# Charging.net
KiCad netlist of a schematic drawn in Altium Designer
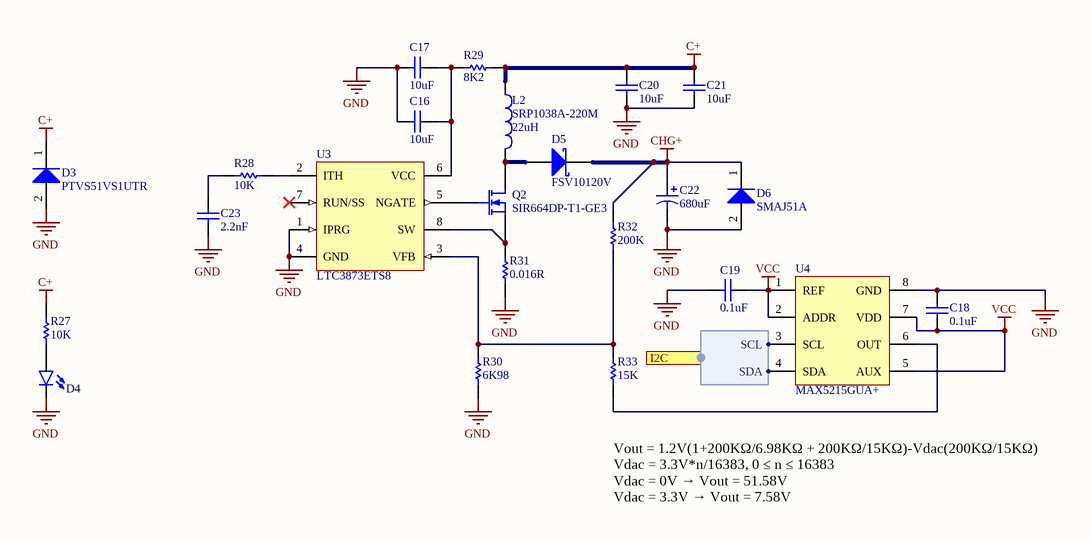
[diagram p0: Charging.SchDoc]

(export (version "E")
  (design (tool "Eeschema 10.0.6"))
  (components
    (comp (ref "C16")
      (value "10uF")
      (footprint "C0603[1608X92]")
      (description "10uF 16V 10% 0603 (1608 Metric)")
      (fields (field (name "PARTNUMBER") "GRM188R61C106KAALD") (field (name "MANUFACTURER") "Murata"))
      (libsource (lib "Capacitors") (part "CAP_10uF_16V_0603_10%"))
    )
    (comp (ref "C17")
      (value "10uF")
      (footprint "C0603[1608X92]")
      (description "10uF 16V 10% 0603 (1608 Metric)")
      (fields (field (name "PARTNUMBER") "GRM188R61C106KAALD") (field (name "MANUFACTURER") "Murata"))
      (libsource (lib "Capacitors") (part "CAP_10uF_16V_0603_10%"))
    )
    (comp (ref "C18")
      (value "0.1uF")
      (footprint "C0603[1608X92]")
      (description "0.1uF 6.3V 10% 0603 (1608 Metric)")
      (fields (field (name "PARTNUMBER") "GRM188R70J104KA01D") (field (name "MANUFACTURER") "Murata"))
      (libsource (lib "Capacitors") (part "CAP_0.1uF_6.3V_0603_10%"))
    )
    (comp (ref "C19")
      (value "0.1uF")
      (footprint "C0603[1608X92]")
      (description "0.1uF 6.3V 10% 0603 (1608 Metric)")
      (fields (field (name "PARTNUMBER") "GRM188R70J104KA01D") (field (name "MANUFACTURER") "Murata"))
      (libsource (lib "Capacitors") (part "CAP_0.1uF_6.3V_0603_10%"))
    )
    (comp (ref "C20")
      (value "10uF")
      (footprint "C1206[3216X160]")
      (description "10uF 50V 20% 1206 (3216 Metric)")
      (fields (field (name "TOLERANCE") "20%") (field (name "PARTNUMBER") "UMK316BBJ106ML-T"))
      (libsource (lib "Capacitors") (part "CAP_10uF_50V_1206_20%"))
    )
    (comp (ref "C21")
      (value "10uF")
      (footprint "C1206[3216X160]")
      (description "10uF 50V 20% 1206 (3216 Metric)")
      (fields (field (name "TOLERANCE") "20%") (field (name "PARTNUMBER") "UMK316BBJ106ML-T"))
      (libsource (lib "Capacitors") (part "CAP_10uF_50V_1206_20%"))
    )
    (comp (ref "C22")
      (value "680uF")
      (footprint "CAP-ELECTROLYTIC[10.0x12.6]")
      (description "180uF 50V 20%")
      (fields (field (name "PARTNUMBER") "PCR1H181MCL1GS") (field (name "MANUFACTURER") "Nichicon"))
      (libsource (lib "Capacitors") (part "CAP_180uF_50V_20%"))
    )
    (comp (ref "C23")
      (value "2.2nF")
      (footprint "C0603[1608X92]")
      (description "2.2nF 50V 5% 0603 (1608 Metric)")
      (fields (field (name "PARTNUMBER") "GRM1885C1H222JA01D") (field (name "MANUFACTURER") "Murata"))
      (libsource (lib "Capacitors") (part "CAP_2.2nF_50V_0603_5%"))
    )
    (comp (ref "D3")
      (value "PTVS51VS1UTR")
      (footprint "SOD-123W")
      (fields (field (name "PARTNUMBER") "PTVS51VS1UTR,115") (field (name "MANUFACTURER") "NXP"))
      (libsource (lib "Diodes") (part "PTVS51VS1UTR,115"))
    )
    (comp (ref "D4")
      (value "LED_0603_GREEN_5mA")
      (footprint "LED0603")
      (fields (field (name "PARTNUMBER") "LTST-C193TGKT-5A") (field (name "MANUFACTURER") "Lite-On Inc."))
      (libsource (lib "LEDs") (part "LED_0603_GREEN_5mA"))
    )
    (comp (ref "D5")
      (value "FSV10120V")
      (footprint "TO-277")
      (description "Schottky Diodes & Rectifiers 10 Amp 120V Schottky Rectifier")
      (fields (field (name "MANUFACTURER") "Fairchild Semiconductor"))
      (libsource (lib "Diodes") (part "FSV10120V"))
    )
    (comp (ref "D6")
      (value "SMAJ51A")
      (footprint "DO-214AC")
      (fields (field (name "PARTNUMBER") "SMAJ51A-E3/61") (field (name "MANUFACTURER") "Vishay"))
      (libsource (lib "Diodes") (part "SMAJ51A-E3/61"))
    )
    (comp (ref "L2")
      (value "SRP1038A-220M")
      (footprint "SRP1038A")
      (description "22uH 20% 7A 1038")
      (fields (field (name "ALTIUM_VALUE") "22uH") (field (name "MANUFACTURER") "Bourns"))
      (libsource (lib "Inductors") (part "SRP1038A-220M"))
    )
    (comp (ref "Q2")
      (value "SIR664DP-T1-GE3")
      (footprint "PowerPak-8")
      (description "N-Channel MOSFET")
      (fields (field (name "MANUFACTURER") "Vishay"))
      (libsource (lib "MOSFETs") (part "SIR664DP-T1-GE3"))
    )
    (comp (ref "R27")
      (value "10K")
      (footprint "R0603[1608]")
      (description "10K 0.25W 1% 0603 (1005 Metric)")
      (fields (field (name "POWER") "0.25W") (field (name "TOLERANCE") "1%"))
      (libsource (lib "Resistors") (part "RES_10K_0603_1%"))
    )
    (comp (ref "R28")
      (value "10K")
      (footprint "R0603[1608]")
      (description "10K 0.25W 1% 0603 (1005 Metric)")
      (fields (field (name "MANUFACTURER") "Vishay") (field (name "PARTNUMBER") "RCS060310K0FKEA"))
      (libsource (lib "Resistors") (part "RES_10K_0603_1%"))
    )
    (comp (ref "R29")
      (value "8K2")
      (footprint "R0603[1608]")
      (description "8K2 0.25W 1% 0603 (1005 Metric)")
      (fields (field (name "MANUFACTURER") "Vishay") (field (name "PARTNUMBER") "CRCW06038K20FKEAHP"))
      (libsource (lib "Resistors") (part "RES_8K2_0603_1%"))
    )
    (comp (ref "R30")
      (value "6K98")
      (footprint "R0603[1608]")
      (description "6K98 0.25W 1% 0603 (1005 Metric)")
      (fields (field (name "MANUFACTURER") "Vishay / Dale") (field (name "PARTNUMBER") "CRCW06036K98FKEAHP"))
      (libsource (lib "Resistors") (part "RES_6K98_0603_1%"))
    )
    (comp (ref "R31")
      (value "0.016R")
      (footprint "R1206[3216]")
      (description "0.016R 1W 1% 1206 (3216 Metric)")
      (fields (field (name "POWER") "1W") (field (name "TOLERANCE") "1%"))
      (libsource (lib "Resistors") (part "RES_0.016R_1206_1%"))
    )
    (comp (ref "R32")
      (value "200K")
      (footprint "R0603[1608]")
      (description "200K 0.25W 1% 0603 (1005 Metric)")
      (fields (field (name "MANUFACTURER") "Rohm Semiconductor") (field (name "PARTNUMBER") "ESR03EZPJ204"))
      (libsource (lib "Resistors") (part "RES_200K_0603_1%"))
    )
    (comp (ref "R33")
      (value "15K")
      (footprint "R0603[1608]")
      (description "15K 0.25W 1% 0603 (1005 Metric)")
      (fields (field (name "MANUFACTURER") "Vishay / Dale") (field (name "PARTNUMBER") "CRCW060315K0FKEAHP"))
      (libsource (lib "Resistors") (part "RES_15K_0603_1%"))
    )
    (comp (ref "U3")
      (value "LTC3873ETS8")
      (footprint "SOT-23-8")
      (fields (field (name "PARTNUMBER") "LTC3873ETS8#PBF") (field (name "MANUFACTURER") "Linear Technology"))
      (libsource (lib "ICs") (part "LTC3873ETS8"))
    )
    (comp (ref "U4")
      (value "MAX5215GUA+")
      (footprint "MSOP-8")
      (description "14 Bit Digital to Analog Converter")
      (fields (field (name "MANUFACTURER") "Maxim Integrated"))
      (libsource (lib "ICs") (part "MAX5215GUA+"))
    )
  )
  (nets
    (net (code "2") (name "/SCL") (class "Default")
      (node (ref "U4") (pin "3") (pinfunction "SCL_3") (pintype "passive"))
    )
    (net (code "3") (name "/SDA") (class "Default")
      (node (ref "U4") (pin "4") (pinfunction "SDA_4") (pintype "passive"))
    )
    (net (code "5") (name "C+") (class "Default")
      (node (ref "C20") (pin "2") (pinfunction "2_2") (pintype "passive"))
      (node (ref "C21") (pin "2") (pinfunction "2_2") (pintype "passive"))
      (node (ref "D3") (pin "1") (pinfunction "K_1") (pintype "passive"))
      (node (ref "L2") (pin "1") (pinfunction "1_1") (pintype "passive"))
      (node (ref "R27") (pin "2") (pinfunction "2_2") (pintype "passive"))
      (node (ref "R29") (pin "2") (pinfunction "2_2") (pintype "passive"))
    )
    (net (code "6") (name "CHG+") (class "Default")
      (node (ref "C22") (pin "1") (pinfunction "1_1") (pintype "passive"))
      (node (ref "D5") (pin "1") (pinfunction "K_1") (pintype "passive"))
      (node (ref "D6") (pin "1") (pinfunction "K_1") (pintype "passive"))
      (node (ref "R32") (pin "2") (pinfunction "2_2") (pintype "passive"))
    )
    (net (code "7") (name "GND") (class "Default")
      (node (ref "C16") (pin "1") (pinfunction "1_1") (pintype "passive"))
      (node (ref "C17") (pin "1") (pinfunction "1_1") (pintype "passive"))
      (node (ref "C18") (pin "1") (pinfunction "1_1") (pintype "passive"))
      (node (ref "C19") (pin "2") (pinfunction "2_2") (pintype "passive"))
      (node (ref "C20") (pin "1") (pinfunction "1_1") (pintype "passive"))
      (node (ref "C21") (pin "1") (pinfunction "1_1") (pintype "passive"))
      (node (ref "C22") (pin "2") (pinfunction "2_2") (pintype "passive"))
      (node (ref "C23") (pin "1") (pinfunction "1_1") (pintype "passive"))
      (node (ref "D3") (pin "2") (pinfunction "A_2") (pintype "passive"))
      (node (ref "D4") (pin "C") (pinfunction "C_C") (pintype "passive"))
      (node (ref "D6") (pin "2") (pinfunction "A_2") (pintype "passive"))
      (node (ref "R30") (pin "1") (pinfunction "1_1") (pintype "passive"))
      (node (ref "R31") (pin "1") (pinfunction "1_1") (pintype "passive"))
      (node (ref "U3") (pin "1") (pinfunction "IPRG_1") (pintype "input"))
      (node (ref "U3") (pin "4") (pinfunction "GND_4") (pintype "power_in"))
      (node (ref "U4") (pin "8") (pinfunction "GND_8") (pintype "power_in"))
    )
    (net (code "8") (name "Net-(C23-Pad2)") (class "Default")
      (node (ref "C23") (pin "2") (pinfunction "2_2") (pintype "passive"))
      (node (ref "R28") (pin "1") (pinfunction "1_1") (pintype "passive"))
    )
    (net (code "9") (name "Net-(D4-PadA)") (class "Default")
      (node (ref "D4") (pin "A") (pinfunction "A_A") (pintype "passive"))
      (node (ref "R27") (pin "1") (pinfunction "1_1") (pintype "passive"))
    )
    (net (code "10") (name "Net-(D5-A)") (class "Default")
      (node (ref "D5") (pin "2") (pinfunction "A_2") (pintype "passive"))
      (node (ref "L2") (pin "2") (pinfunction "2_2") (pintype "passive"))
      (node (ref "Q2") (pin "3") (pinfunction "D_3") (pintype "passive"))
    )
    (net (code "11") (name "Net-(Q2-G)") (class "Default")
      (node (ref "Q2") (pin "2") (pinfunction "G_2") (pintype "passive"))
      (node (ref "U3") (pin "5") (pinfunction "NGATE_5") (pintype "output"))
    )
    (net (code "12") (name "Net-(Q2-S)") (class "Default")
      (node (ref "Q2") (pin "1") (pinfunction "S_1") (pintype "passive"))
      (node (ref "R31") (pin "2") (pinfunction "2_2") (pintype "passive"))
      (node (ref "U3") (pin "8") (pinfunction "SW_8") (pintype "passive"))
    )
    (net (code "13") (name "Net-(U3-ITH)") (class "Default")
      (node (ref "R28") (pin "2") (pinfunction "2_2") (pintype "passive"))
      (node (ref "U3") (pin "2") (pinfunction "ITH_2") (pintype "passive"))
    )
    (net (code "14") (name "Net-(U3-VCC)") (class "Default")
      (node (ref "C16") (pin "2") (pinfunction "2_2") (pintype "passive"))
      (node (ref "C17") (pin "2") (pinfunction "2_2") (pintype "passive"))
      (node (ref "R29") (pin "1") (pinfunction "1_1") (pintype "passive"))
      (node (ref "U3") (pin "6") (pinfunction "VCC_6") (pintype "power_in"))
    )
    (net (code "15") (name "Net-(U3-VFB)") (class "Default")
      (node (ref "R30") (pin "2") (pinfunction "2_2") (pintype "passive"))
      (node (ref "R32") (pin "1") (pinfunction "1_1") (pintype "passive"))
      (node (ref "R33") (pin "2") (pinfunction "2_2") (pintype "passive"))
      (node (ref "U3") (pin "3") (pinfunction "VFB_3") (pintype "input"))
    )
    (net (code "16") (name "Net-(U4-OUT)") (class "Default")
      (node (ref "R33") (pin "1") (pinfunction "1_1") (pintype "passive"))
      (node (ref "U4") (pin "6") (pinfunction "OUT_6") (pintype "passive"))
    )
    (net (code "17") (name "VCC") (class "Default")
      (node (ref "C18") (pin "2") (pinfunction "2_2") (pintype "passive"))
      (node (ref "C19") (pin "1") (pinfunction "1_1") (pintype "passive"))
      (node (ref "U4") (pin "1") (pinfunction "REF_1") (pintype "passive"))
      (node (ref "U4") (pin "2") (pinfunction "ADDR_2") (pintype "passive"))
      (node (ref "U4") (pin "5") (pinfunction "AUX_5") (pintype "passive"))
      (node (ref "U4") (pin "7") (pinfunction "VDD_7") (pintype "power_in"))
    )
    (net (code "18") (name "unconnected-(U3-RUN{slash}SS-Pad7)") (class "Default")
      (node (ref "U3") (pin "7") (pinfunction "RUN/SS_7") (pintype "input+no_connect"))
    )
  )
)
